# GPS_chip.net
KiCad netlist of a schematic drawn in EAGLE
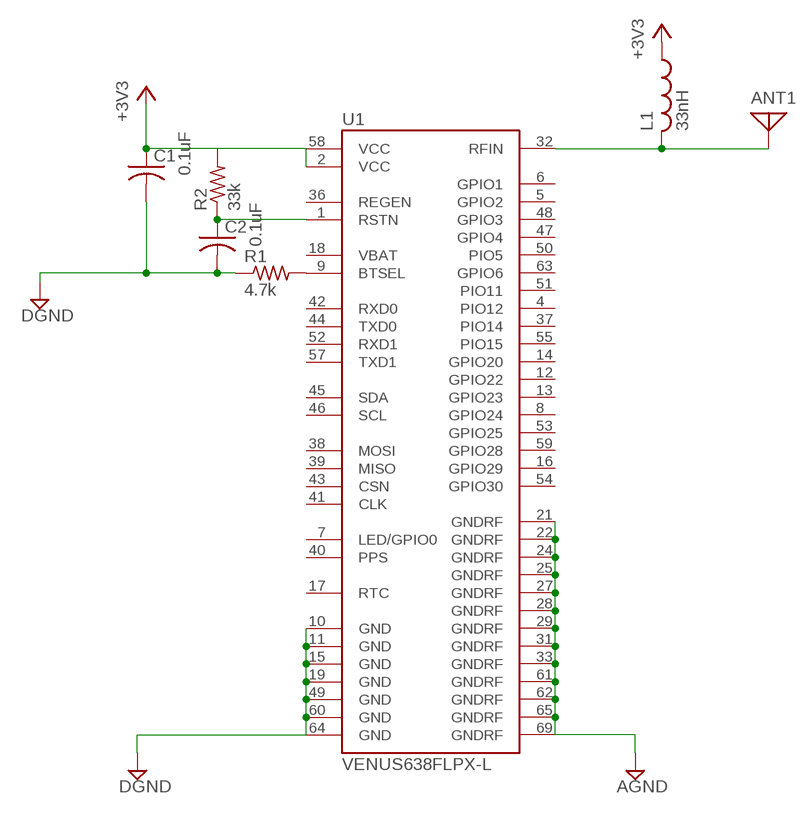
[diagram p0: schematic, sheet 1]

(export (version "E")
  (design (tool "Eeschema 10.0.6"))
  (components
    (comp (ref "ANT1")
      (value "ANTENNA")
      (footprint "eagle-import:PAD-01")
      (libsource (lib "eagle-import") (part "ANTENNA"))
    )
    (comp (ref "C1")
      (value "C-USC0603")
      (footprint "eagle-import:C0603")
      (fields (field (name "CAP") "0.1uF"))
      (libsource (lib "eagle-import") (part "C-USC0603"))
    )
    (comp (ref "C2")
      (value "C-USC0603")
      (footprint "eagle-import:C0603")
      (fields (field (name "CAP") "0.1uF"))
      (libsource (lib "eagle-import") (part "C-USC0603"))
    )
    (comp (ref "L1")
      (value "33nH")
      (footprint "eagle-import:L4532P")
      (libsource (lib "eagle-import") (part "L-USL4532P"))
    )
    (comp (ref "R1")
      (value "4.7k")
      (footprint "eagle-import:R0603")
      (libsource (lib "eagle-import") (part "R-US_R0603"))
    )
    (comp (ref "R2")
      (value "33k")
      (footprint "eagle-import:R0603")
      (libsource (lib "eagle-import") (part "R-US_R0603"))
    )
    (comp (ref "U1")
      (value "VENUS638FLPX-L")
      (footprint "eagle-import:VENUS638FLPX")
      (libsource (lib "eagle-import") (part "VENUS638FLPX-L"))
    )
  )
  (nets
    (net (code "1") (name "+3V3") (class "Default")
      (node (ref "C1") (pin "1") (pinfunction "1_1") (pintype "passive"))
      (node (ref "L1") (pin "1") (pinfunction "1_1") (pintype "passive"))
      (node (ref "R2") (pin "2") (pinfunction "2_2") (pintype "passive"))
      (node (ref "U1") (pin "2") (pinfunction "VCC_2") (pintype "bidirectional"))
      (node (ref "U1") (pin "58") (pinfunction "VCC_58") (pintype "bidirectional"))
    )
    (net (code "2") (name "AGND") (class "Default")
      (node (ref "U1") (pin "21") (pinfunction "GNDRF_21") (pintype "bidirectional"))
      (node (ref "U1") (pin "22") (pinfunction "GNDRF_22") (pintype "bidirectional"))
      (node (ref "U1") (pin "24") (pinfunction "GNDRF_24") (pintype "bidirectional"))
      (node (ref "U1") (pin "25") (pinfunction "GNDRF_25") (pintype "bidirectional"))
      (node (ref "U1") (pin "27") (pinfunction "GNDRF_27") (pintype "bidirectional"))
      (node (ref "U1") (pin "28") (pinfunction "GNDRF_28") (pintype "bidirectional"))
      (node (ref "U1") (pin "29") (pinfunction "GNDRF_29") (pintype "bidirectional"))
      (node (ref "U1") (pin "31") (pinfunction "GNDRF_31") (pintype "bidirectional"))
      (node (ref "U1") (pin "33") (pinfunction "GNDRF_33") (pintype "bidirectional"))
      (node (ref "U1") (pin "61") (pinfunction "GNDRF_61") (pintype "bidirectional"))
      (node (ref "U1") (pin "62") (pinfunction "GNDRF_62") (pintype "bidirectional"))
      (node (ref "U1") (pin "65") (pinfunction "GNDRF_65") (pintype "bidirectional"))
      (node (ref "U1") (pin "69") (pinfunction "GNDRF_69") (pintype "bidirectional"))
    )
    (net (code "3") (name "DGND") (class "Default")
      (node (ref "C1") (pin "2") (pinfunction "2_2") (pintype "passive"))
      (node (ref "C2") (pin "2") (pinfunction "2_2") (pintype "passive"))
      (node (ref "R1") (pin "1") (pinfunction "1_1") (pintype "passive"))
      (node (ref "U1") (pin "10") (pinfunction "GND_10") (pintype "bidirectional"))
      (node (ref "U1") (pin "11") (pinfunction "GND_11") (pintype "bidirectional"))
      (node (ref "U1") (pin "15") (pinfunction "GND_15") (pintype "bidirectional"))
      (node (ref "U1") (pin "19") (pinfunction "GND_19") (pintype "bidirectional"))
      (node (ref "U1") (pin "49") (pinfunction "GND_49") (pintype "bidirectional"))
      (node (ref "U1") (pin "60") (pinfunction "GND_60") (pintype "bidirectional"))
      (node (ref "U1") (pin "64") (pinfunction "GND_64") (pintype "bidirectional"))
    )
    (net (code "4") (name "Net-(U1-BTSEL)") (class "Default")
      (node (ref "R1") (pin "2") (pinfunction "2_2") (pintype "passive"))
      (node (ref "U1") (pin "9") (pinfunction "BTSEL_9") (pintype "bidirectional"))
    )
    (net (code "5") (name "Net-(U1-RFIN)") (class "Default")
      (node (ref "ANT1") (pin "1") (pinfunction "1_1") (pintype "output"))
      (node (ref "L1") (pin "2") (pinfunction "2_2") (pintype "passive"))
      (node (ref "U1") (pin "32") (pinfunction "RFIN_32") (pintype "bidirectional"))
    )
    (net (code "6") (name "Net-(U1-RSTN)") (class "Default")
      (node (ref "C2") (pin "1") (pinfunction "1_1") (pintype "passive"))
      (node (ref "R2") (pin "1") (pinfunction "1_1") (pintype "passive"))
      (node (ref "U1") (pin "1") (pinfunction "RSTN_1") (pintype "bidirectional"))
    )
    (net (code "7") (name "unconnected-(U1-CLK-Pad41)") (class "Default")
      (node (ref "U1") (pin "41") (pinfunction "CLK_41") (pintype "bidirectional"))
    )
    (net (code "8") (name "unconnected-(U1-CSN-Pad43)") (class "Default")
      (node (ref "U1") (pin "43") (pinfunction "CSN_43") (pintype "bidirectional"))
    )
    (net (code "9") (name "unconnected-(U1-GPIO1-Pad6)") (class "Default")
      (node (ref "U1") (pin "6") (pinfunction "GPIO1_6") (pintype "bidirectional"))
    )
    (net (code "10") (name "unconnected-(U1-GPIO2-Pad5)") (class "Default")
      (node (ref "U1") (pin "5") (pinfunction "GPIO2_5") (pintype "bidirectional"))
    )
    (net (code "11") (name "unconnected-(U1-GPIO3-Pad48)") (class "Default")
      (node (ref "U1") (pin "48") (pinfunction "GPIO3_48") (pintype "bidirectional"))
    )
    (net (code "12") (name "unconnected-(U1-GPIO4-Pad47)") (class "Default")
      (node (ref "U1") (pin "47") (pinfunction "GPIO4_47") (pintype "bidirectional"))
    )
    (net (code "13") (name "unconnected-(U1-GPIO6-Pad63)") (class "Default")
      (node (ref "U1") (pin "63") (pinfunction "GPIO6_63") (pintype "bidirectional"))
    )
    (net (code "14") (name "unconnected-(U1-GPIO20-Pad14)") (class "Default")
      (node (ref "U1") (pin "14") (pinfunction "GPIO20_14") (pintype "bidirectional"))
    )
    (net (code "15") (name "unconnected-(U1-GPIO22-Pad12)") (class "Default")
      (node (ref "U1") (pin "12") (pinfunction "GPIO22_12") (pintype "bidirectional"))
    )
    (net (code "16") (name "unconnected-(U1-GPIO23-Pad13)") (class "Default")
      (node (ref "U1") (pin "13") (pinfunction "GPIO23_13") (pintype "bidirectional"))
    )
    (net (code "17") (name "unconnected-(U1-GPIO24-Pad8)") (class "Default")
      (node (ref "U1") (pin "8") (pinfunction "GPIO24_8") (pintype "bidirectional"))
    )
    (net (code "18") (name "unconnected-(U1-GPIO25-Pad53)") (class "Default")
      (node (ref "U1") (pin "53") (pinfunction "GPIO25_53") (pintype "bidirectional"))
    )
    (net (code "19") (name "unconnected-(U1-GPIO28-Pad59)") (class "Default")
      (node (ref "U1") (pin "59") (pinfunction "GPIO28_59") (pintype "bidirectional"))
    )
    (net (code "20") (name "unconnected-(U1-GPIO29-Pad16)") (class "Default")
      (node (ref "U1") (pin "16") (pinfunction "GPIO29_16") (pintype "bidirectional"))
    )
    (net (code "21") (name "unconnected-(U1-GPIO30-Pad54)") (class "Default")
      (node (ref "U1") (pin "54") (pinfunction "GPIO30_54") (pintype "bidirectional"))
    )
    (net (code "22") (name "unconnected-(U1-LED{slash}GPIO0-Pad7)") (class "Default")
      (node (ref "U1") (pin "7") (pinfunction "LED/GPIO0_7") (pintype "bidirectional"))
    )
    (net (code "23") (name "unconnected-(U1-MISO-Pad39)") (class "Default")
      (node (ref "U1") (pin "39") (pinfunction "MISO_39") (pintype "bidirectional"))
    )
    (net (code "24") (name "unconnected-(U1-MOSI-Pad38)") (class "Default")
      (node (ref "U1") (pin "38") (pinfunction "MOSI_38") (pintype "bidirectional"))
    )
    (net (code "25") (name "unconnected-(U1-PIO5-Pad50)") (class "Default")
      (node (ref "U1") (pin "50") (pinfunction "PIO5_50") (pintype "bidirectional"))
    )
    (net (code "26") (name "unconnected-(U1-PIO11-Pad51)") (class "Default")
      (node (ref "U1") (pin "51") (pinfunction "PIO11_51") (pintype "bidirectional"))
    )
    (net (code "27") (name "unconnected-(U1-PIO12-Pad4)") (class "Default")
      (node (ref "U1") (pin "4") (pinfunction "PIO12_4") (pintype "bidirectional"))
    )
    (net (code "28") (name "unconnected-(U1-PIO14-Pad37)") (class "Default")
      (node (ref "U1") (pin "37") (pinfunction "PIO14_37") (pintype "bidirectional"))
    )
    (net (code "29") (name "unconnected-(U1-PIO15-Pad55)") (class "Default")
      (node (ref "U1") (pin "55") (pinfunction "PIO15_55") (pintype "bidirectional"))
    )
    (net (code "30") (name "unconnected-(U1-PPS-Pad40)") (class "Default")
      (node (ref "U1") (pin "40") (pinfunction "PPS_40") (pintype "bidirectional"))
    )
    (net (code "31") (name "unconnected-(U1-REGEN-Pad36)") (class "Default")
      (node (ref "U1") (pin "36") (pinfunction "REGEN_36") (pintype "bidirectional"))
    )
    (net (code "32") (name "unconnected-(U1-RTC-Pad17)") (class "Default")
      (node (ref "U1") (pin "17") (pinfunction "RTC_17") (pintype "bidirectional"))
    )
    (net (code "33") (name "unconnected-(U1-RXD0-Pad42)") (class "Default")
      (node (ref "U1") (pin "42") (pinfunction "RXD0_42") (pintype "bidirectional"))
    )
    (net (code "34") (name "unconnected-(U1-RXD1-Pad52)") (class "Default")
      (node (ref "U1") (pin "52") (pinfunction "RXD1_52") (pintype "bidirectional"))
    )
    (net (code "35") (name "unconnected-(U1-SCL-Pad46)") (class "Default")
      (node (ref "U1") (pin "46") (pinfunction "SCL_46") (pintype "bidirectional"))
    )
    (net (code "36") (name "unconnected-(U1-SDA-Pad45)") (class "Default")
      (node (ref "U1") (pin "45") (pinfunction "SDA_45") (pintype "bidirectional"))
    )
    (net (code "37") (name "unconnected-(U1-TXD0-Pad44)") (class "Default")
      (node (ref "U1") (pin "44") (pinfunction "TXD0_44") (pintype "bidirectional"))
    )
    (net (code "38") (name "unconnected-(U1-TXD1-Pad57)") (class "Default")
      (node (ref "U1") (pin "57") (pinfunction "TXD1_57") (pintype "bidirectional"))
    )
    (net (code "39") (name "unconnected-(U1-VBAT-Pad18)") (class "Default")
      (node (ref "U1") (pin "18") (pinfunction "VBAT_18") (pintype "bidirectional"))
    )
  )
)
